# PM_proto_2-alt.net
KiCad netlist of a schematic drawn in EAGLE
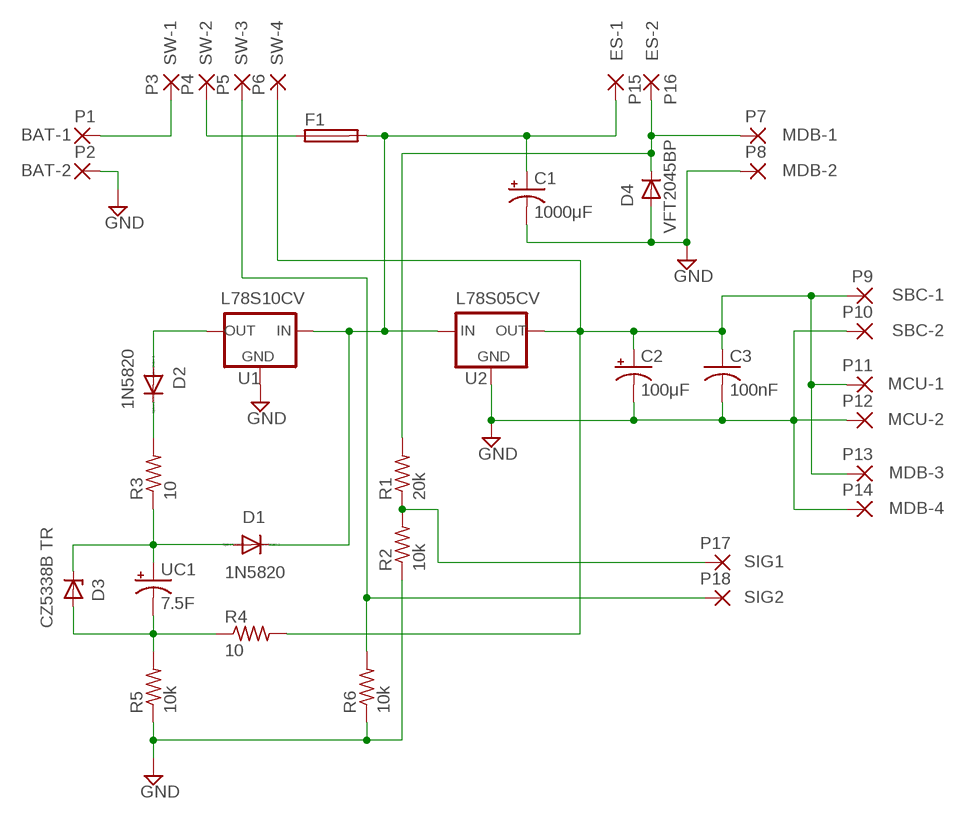
[diagram p0: schematic, sheet 1]

(export (version "E")
  (design (tool "Eeschema 10.0.6"))
  (components
    (comp (ref "C1")
      (value "1000μF")
      (footprint "eagle-import:E7,5-16")
      (libsource (lib "eagle-import") (part "CPOL-USE7.5-16"))
    )
    (comp (ref "C2")
      (value "100μF")
      (footprint "eagle-import:E2,5-6E")
      (libsource (lib "eagle-import") (part "CPOL-USE2,5-6E"))
    )
    (comp (ref "C3")
      (value "100nF")
      (footprint "eagle-import:C050-024X044")
      (libsource (lib "eagle-import") (part "C-US050-024X044"))
    )
    (comp (ref "D1")
      (value "1N5820")
      (footprint "eagle-import:DO41-10")
      (libsource (lib "eagle-import") (part "1N4004"))
    )
    (comp (ref "D2")
      (value "1N5820")
      (footprint "eagle-import:DO41-10")
      (libsource (lib "eagle-import") (part "1N4004"))
    )
    (comp (ref "D3")
      (value "CZ5338B TR")
      (footprint "eagle-import:DO41Z10")
      (libsource (lib "eagle-import") (part "1N4728"))
    )
    (comp (ref "D4")
      (value "VFT2045BP")
      (footprint "eagle-import:VFT2045BP")
      (libsource (lib "eagle-import") (part "VFT2045BP"))
    )
    (comp (ref "F1")
      (value "0297015FUSE")
      (footprint "eagle-import:0297015HOLDER")
      (libsource (lib "eagle-import") (part "0297015FUSE"))
    )
    (comp (ref "P1")
      (value "BAT-1")
      (footprint "eagle-import:1,6_0,8")
      (libsource (lib "eagle-import") (part "1,6/0,8"))
    )
    (comp (ref "P2")
      (value "BAT-2")
      (footprint "eagle-import:1,6_0,8")
      (libsource (lib "eagle-import") (part "1,6/0,8"))
    )
    (comp (ref "P3")
      (value "SW-1")
      (footprint "eagle-import:1,6_0,8")
      (libsource (lib "eagle-import") (part "1,6/0,8"))
    )
    (comp (ref "P4")
      (value "SW-2")
      (footprint "eagle-import:1,6_0,8")
      (libsource (lib "eagle-import") (part "1,6/0,8"))
    )
    (comp (ref "P5")
      (value "SW-3")
      (footprint "eagle-import:1,6_0,8")
      (libsource (lib "eagle-import") (part "1,6/0,8"))
    )
    (comp (ref "P6")
      (value "SW-4")
      (footprint "eagle-import:1,6_0,8")
      (libsource (lib "eagle-import") (part "1,6/0,8"))
    )
    (comp (ref "P7")
      (value "MDB-1")
      (footprint "eagle-import:1,6_0,8")
      (libsource (lib "eagle-import") (part "1,6/0,8"))
    )
    (comp (ref "P8")
      (value "MDB-2")
      (footprint "eagle-import:1,6_0,8")
      (libsource (lib "eagle-import") (part "1,6/0,8"))
    )
    (comp (ref "P9")
      (value "SBC-1")
      (footprint "eagle-import:1,6_0,8")
      (libsource (lib "eagle-import") (part "1,6/0,8"))
    )
    (comp (ref "P10")
      (value "SBC-2")
      (footprint "eagle-import:1,6_0,8")
      (libsource (lib "eagle-import") (part "1,6/0,8"))
    )
    (comp (ref "P11")
      (value "MCU-1")
      (footprint "eagle-import:1,6_0,8")
      (libsource (lib "eagle-import") (part "1,6/0,8"))
    )
    (comp (ref "P12")
      (value "MCU-2")
      (footprint "eagle-import:1,6_0,8")
      (libsource (lib "eagle-import") (part "1,6/0,8"))
    )
    (comp (ref "P13")
      (value "MDB-3")
      (footprint "eagle-import:1,6_0,8")
      (libsource (lib "eagle-import") (part "1,6/0,8"))
    )
    (comp (ref "P14")
      (value "MDB-4")
      (footprint "eagle-import:1,6_0,8")
      (libsource (lib "eagle-import") (part "1,6/0,8"))
    )
    (comp (ref "P15")
      (value "ES-1")
      (footprint "eagle-import:1,6_0,8")
      (libsource (lib "eagle-import") (part "1,6/0,8"))
    )
    (comp (ref "P16")
      (value "ES-2")
      (footprint "eagle-import:1,6_0,8")
      (libsource (lib "eagle-import") (part "1,6/0,8"))
    )
    (comp (ref "P17")
      (value "SIG1")
      (footprint "eagle-import:1,6_0,8")
      (libsource (lib "eagle-import") (part "1,6/0,8"))
    )
    (comp (ref "P18")
      (value "SIG2")
      (footprint "eagle-import:1,6_0,8")
      (libsource (lib "eagle-import") (part "1,6/0,8"))
    )
    (comp (ref "R1")
      (value "20k")
      (footprint "eagle-import:0204_7")
      (libsource (lib "eagle-import") (part "R-US_0204/7"))
    )
    (comp (ref "R2")
      (value "10k")
      (footprint "eagle-import:0204_7")
      (libsource (lib "eagle-import") (part "R-US_0204/7"))
    )
    (comp (ref "R3")
      (value "10")
      (footprint "eagle-import:TNP10SC10R0FE")
      (libsource (lib "eagle-import") (part "TNP10SC10R0FE"))
    )
    (comp (ref "R4")
      (value "10")
      (footprint "eagle-import:TNP10SC10R0FE")
      (libsource (lib "eagle-import") (part "TNP10SC10R0FE"))
    )
    (comp (ref "R5")
      (value "10k")
      (footprint "eagle-import:0204_7")
      (libsource (lib "eagle-import") (part "R-US_0204/7"))
    )
    (comp (ref "R6")
      (value "10k")
      (footprint "eagle-import:0204_7")
      (libsource (lib "eagle-import") (part "R-US_0204/7"))
    )
    (comp (ref "U1")
      (value "L78S10CV")
      (footprint "eagle-import:78XXS")
      (libsource (lib "eagle-import") (part "78XXS"))
    )
    (comp (ref "U2")
      (value "L78S05CV")
      (footprint "eagle-import:78XXS")
      (fields (field (name "SPICEPREFIX") "J"))
      (libsource (lib "eagle-import") (part "78XXS"))
    )
    (comp (ref "UC1")
      (value "7.5F")
      (footprint "eagle-import:SCMT32D755MRBB0")
      (libsource (lib "eagle-import") (part "SCMT32D755MRBB0"))
    )
  )
  (nets
    (net (code "1") (name "GND") (class "Default")
      (node (ref "C1") (pin "-") (pinfunction "-_-") (pintype "passive"))
      (node (ref "C2") (pin "-") (pinfunction "-_-") (pintype "passive"))
      (node (ref "C3") (pin "2") (pinfunction "2_2") (pintype "passive"))
      (node (ref "D4") (pin "2") (pinfunction "A_2") (pintype "passive"))
      (node (ref "P10") (pin "1") (pinfunction "P_1") (pintype "passive"))
      (node (ref "P12") (pin "1") (pinfunction "P_1") (pintype "passive"))
      (node (ref "P14") (pin "1") (pinfunction "P_1") (pintype "passive"))
      (node (ref "P2") (pin "1") (pinfunction "P_1") (pintype "passive"))
      (node (ref "P8") (pin "1") (pinfunction "P_1") (pintype "passive"))
      (node (ref "R2") (pin "1") (pinfunction "1_1") (pintype "passive"))
      (node (ref "R5") (pin "1") (pinfunction "1_1") (pintype "passive"))
      (node (ref "R6") (pin "1") (pinfunction "1_1") (pintype "passive"))
      (node (ref "U1") (pin "GND") (pinfunction "GND_GND") (pintype "input"))
      (node (ref "U2") (pin "GND") (pinfunction "GND_GND") (pintype "input"))
    )
    (net (code "2") (name "Net-(D2-PadA)") (class "Default")
      (node (ref "D2") (pin "A") (pinfunction "A_A") (pintype "passive"))
      (node (ref "U1") (pin "OUT") (pinfunction "OUT_OUT") (pintype "passive"))
    )
    (net (code "3") (name "Net-(D2-PadC)") (class "Default")
      (node (ref "D2") (pin "C") (pinfunction "C_C") (pintype "passive"))
      (node (ref "R3") (pin "2") (pinfunction "2_2") (pintype "passive"))
    )
    (net (code "4") (name "Net-(D4-C)") (class "Default")
      (node (ref "D4") (pin "1") (pinfunction "C_1") (pintype "passive"))
      (node (ref "P16") (pin "1") (pinfunction "P_1") (pintype "passive"))
      (node (ref "P7") (pin "1") (pinfunction "P_1") (pintype "passive"))
      (node (ref "R1") (pin "2") (pinfunction "2_2") (pintype "passive"))
    )
    (net (code "5") (name "Net-(P1-P)") (class "Default")
      (node (ref "P1") (pin "1") (pinfunction "P_1") (pintype "passive"))
      (node (ref "P3") (pin "1") (pinfunction "P_1") (pintype "passive"))
    )
    (net (code "6") (name "Net-(P4-P)") (class "Default")
      (node (ref "F1") (pin "1") (pinfunction "1_1") (pintype "passive"))
      (node (ref "F1") (pin "2") (pinfunction "1_2") (pintype "passive"))
      (node (ref "P4") (pin "1") (pinfunction "P_1") (pintype "passive"))
    )
    (net (code "7") (name "Net-(P11-P)") (class "Default")
      (node (ref "C2") (pin "+") (pinfunction "+_+") (pintype "passive"))
      (node (ref "C3") (pin "1") (pinfunction "1_1") (pintype "passive"))
      (node (ref "P11") (pin "1") (pinfunction "P_1") (pintype "passive"))
      (node (ref "P13") (pin "1") (pinfunction "P_1") (pintype "passive"))
      (node (ref "P6") (pin "1") (pinfunction "P_1") (pintype "passive"))
      (node (ref "P9") (pin "1") (pinfunction "P_1") (pintype "passive"))
      (node (ref "R4") (pin "2") (pinfunction "2_2") (pintype "passive"))
      (node (ref "U2") (pin "OUT") (pinfunction "OUT_OUT") (pintype "passive"))
    )
    (net (code "8") (name "Net-(P15-P)") (class "Default")
      (node (ref "C1") (pin "+") (pinfunction "+_+") (pintype "passive"))
      (node (ref "D1") (pin "C") (pinfunction "C_C") (pintype "passive"))
      (node (ref "F1") (pin "3") (pinfunction "2_3") (pintype "passive"))
      (node (ref "F1") (pin "4") (pinfunction "2_4") (pintype "passive"))
      (node (ref "P15") (pin "1") (pinfunction "P_1") (pintype "passive"))
      (node (ref "U1") (pin "IN") (pinfunction "IN_IN") (pintype "input"))
      (node (ref "U2") (pin "IN") (pinfunction "IN_IN") (pintype "input"))
    )
    (net (code "9") (name "Net-(P17-P)") (class "Default")
      (node (ref "P17") (pin "1") (pinfunction "P_1") (pintype "passive"))
      (node (ref "R1") (pin "1") (pinfunction "1_1") (pintype "passive"))
      (node (ref "R2") (pin "2") (pinfunction "2_2") (pintype "passive"))
    )
    (net (code "10") (name "Net-(P18-P)") (class "Default")
      (node (ref "P18") (pin "1") (pinfunction "P_1") (pintype "passive"))
      (node (ref "P5") (pin "1") (pinfunction "P_1") (pintype "passive"))
      (node (ref "R6") (pin "2") (pinfunction "2_2") (pintype "passive"))
    )
    (net (code "11") (name "Net-(UC1-+)") (class "Default")
      (node (ref "D1") (pin "A") (pinfunction "A_A") (pintype "passive"))
      (node (ref "D3") (pin "C") (pinfunction "C_C") (pintype "passive"))
      (node (ref "R3") (pin "1") (pinfunction "1_1") (pintype "passive"))
      (node (ref "UC1") (pin "1") (pinfunction "+_1") (pintype "passive"))
    )
    (net (code "12") (name "Net-(UC1--)") (class "Default")
      (node (ref "D3") (pin "A") (pinfunction "A_A") (pintype "passive"))
      (node (ref "R4") (pin "1") (pinfunction "1_1") (pintype "passive"))
      (node (ref "R5") (pin "2") (pinfunction "2_2") (pintype "passive"))
      (node (ref "UC1") (pin "2") (pinfunction "-_2") (pintype "passive"))
    )
  )
)
